# 3__Sensors.net
KiCad netlist of a schematic drawn in Altium Designer
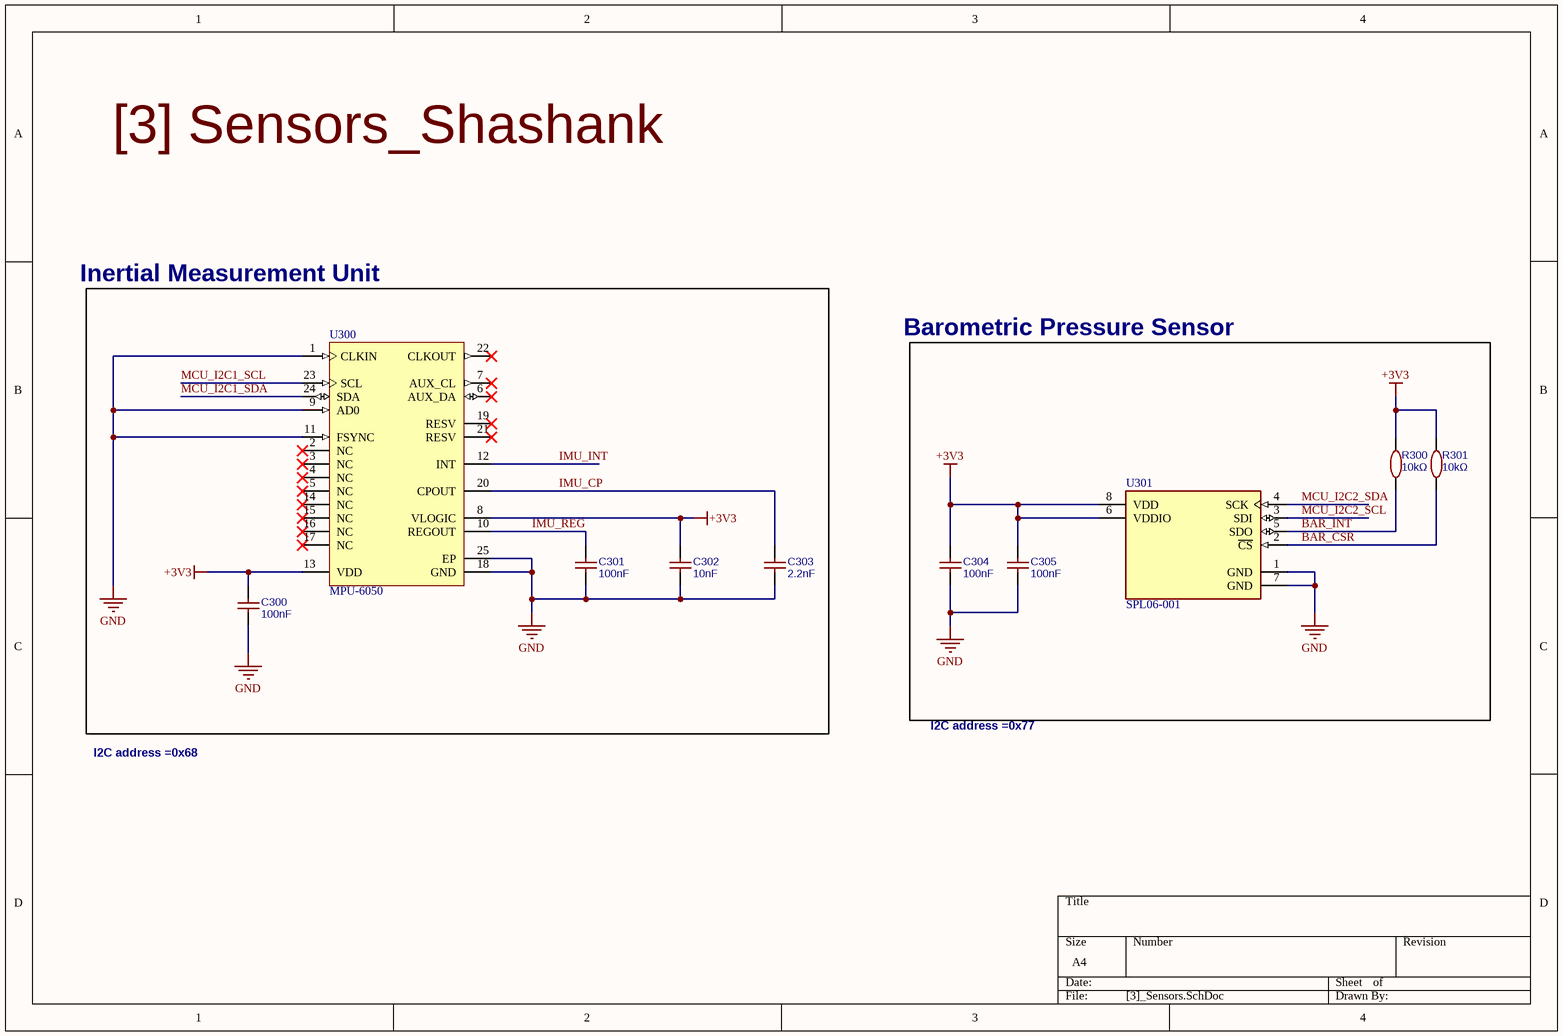
[diagram p0: [3]_Sensors.SchDoc]

(export (version "E")
  (design (tool "Eeschema 10.0.6"))
  (components
    (comp (ref "C300")
      (value "100nF")
      (footprint "C0402")
      (fields (field (name "MANUFACTURER") "FH(风华)") (field (name "MANUFACTURER PART") "0402B471K500NT"))
      (libsource (lib "Power_Lib") (part "470pF"))
    )
    (comp (ref "C301")
      (value "100nF")
      (footprint "C0402")
      (fields (field (name "MANUFACTURER") "FH(风华)") (field (name "MANUFACTURER PART") "0402B471K500NT"))
      (libsource (lib "Power_Lib") (part "470pF"))
    )
    (comp (ref "C302")
      (value "10nF")
      (footprint "C0402")
      (fields (field (name "MANUFACTURER") "FH(风华)") (field (name "MANUFACTURER PART") "0402B471K500NT"))
      (libsource (lib "Power_Lib") (part "470pF"))
    )
    (comp (ref "C303")
      (value "2.2nF")
      (footprint "C0402")
      (fields (field (name "MANUFACTURER") "FH(风华)") (field (name "MANUFACTURER PART") "0402B471K500NT"))
      (libsource (lib "Power_Lib") (part "470pF"))
    )
    (comp (ref "C304")
      (value "100nF")
      (footprint "C0402")
      (fields (field (name "MANUFACTURER") "FH(风华)") (field (name "MANUFACTURER PART") "0402B471K500NT"))
      (libsource (lib "Power_Lib") (part "470pF"))
    )
    (comp (ref "C305")
      (value "100nF")
      (footprint "C0402")
      (fields (field (name "MANUFACTURER") "FH(风华)") (field (name "MANUFACTURER PART") "0402B471K500NT"))
      (libsource (lib "Power_Lib") (part "470pF"))
    )
    (comp (ref "R300")
      (value "10kΩ")
      (footprint "R0402")
      (fields
        (field (name "MANUFACTURER") "UNI-ROYAL(厚声)")
        (field (name "MANUFACTURER PART") "0402WGF1001TCE")
      )
      (libsource (lib "Power_Lib") (part "1kΩ"))
    )
    (comp (ref "R301")
      (value "10kΩ")
      (footprint "R0402")
      (fields
        (field (name "MANUFACTURER") "UNI-ROYAL(厚声)")
        (field (name "MANUFACTURER PART") "0402WGF1001TCE")
      )
      (libsource (lib "Power_Lib") (part "1kΩ"))
    )
    (comp (ref "U300")
      (value "MPU-6050")
      (footprint "IS-QFN-24_V")
      (fields (field (name "MANUFACTURER") "InvenSense"))
      (libsource (lib "Altium Content Vault") (part "IS-MPU-6050-QFN-24"))
    )
    (comp (ref "U301")
      (value "SPL06-001")
      (footprint "FP-BMP280-MFG")
      (description "SENSOR PRESSURE ABS")
      (libsource (lib "Altium Content Vault") (part "69b1aacbb03d82763a43fac02afba64"))
    )
  )
  (nets
    (net (code "1") (name "+3V3") (class "Default")
      (node (ref "C300") (pin "2") (pinfunction "2_2") (pintype "passive"))
      (node (ref "C302") (pin "2") (pinfunction "2_2") (pintype "passive"))
      (node (ref "C304") (pin "2") (pinfunction "2_2") (pintype "passive"))
      (node (ref "C305") (pin "2") (pinfunction "2_2") (pintype "passive"))
      (node (ref "R300") (pin "2") (pinfunction "2_2") (pintype "passive"))
      (node (ref "R301") (pin "2") (pinfunction "2_2") (pintype "passive"))
      (node (ref "U300") (pin "13") (pinfunction "VDD_13") (pintype "power_in"))
      (node (ref "U300") (pin "8") (pinfunction "VLOGIC_8") (pintype "power_in"))
      (node (ref "U301") (pin "6") (pinfunction "VDDIO_6") (pintype "power_in"))
      (node (ref "U301") (pin "8") (pinfunction "VDD_8") (pintype "power_in"))
    )
    (net (code "2") (name "/BAR_CSR") (class "Default")
      (node (ref "R301") (pin "1") (pinfunction "1_1") (pintype "passive"))
      (node (ref "U301") (pin "2") (pinfunction "~{CS}_2") (pintype "input"))
    )
    (net (code "3") (name "/BAR_INT") (class "Default")
      (node (ref "R300") (pin "1") (pinfunction "1_1") (pintype "passive"))
      (node (ref "U301") (pin "5") (pinfunction "SDO_5") (pintype "bidirectional"))
    )
    (net (code "4") (name "/IMU_CP") (class "Default")
      (node (ref "C303") (pin "2") (pinfunction "2_2") (pintype "passive"))
      (node (ref "U300") (pin "20") (pinfunction "CPOUT_20") (pintype "passive"))
    )
    (net (code "5") (name "/IMU_INT") (class "Default")
      (node (ref "U300") (pin "12") (pinfunction "INT_12") (pintype "open_collector"))
    )
    (net (code "6") (name "/IMU_REG") (class "Default")
      (node (ref "C301") (pin "2") (pinfunction "2_2") (pintype "passive"))
      (node (ref "U300") (pin "10") (pinfunction "REGOUT_10") (pintype "passive"))
    )
    (net (code "7") (name "/MCU_I2C1_SCL") (class "Default")
      (node (ref "U300") (pin "23") (pinfunction "SCL_23") (pintype "input"))
    )
    (net (code "8") (name "/MCU_I2C1_SDA") (class "Default")
      (node (ref "U300") (pin "24") (pinfunction "SDA_24") (pintype "bidirectional"))
    )
    (net (code "9") (name "/MCU_I2C2_SCL") (class "Default")
      (node (ref "U301") (pin "3") (pinfunction "SDI_3") (pintype "bidirectional"))
    )
    (net (code "10") (name "/MCU_I2C2_SDA") (class "Default")
      (node (ref "U301") (pin "4") (pinfunction "SCK_4") (pintype "input"))
    )
    (net (code "11") (name "GND") (class "Default")
      (node (ref "C300") (pin "1") (pinfunction "1_1") (pintype "passive"))
      (node (ref "C301") (pin "1") (pinfunction "1_1") (pintype "passive"))
      (node (ref "C302") (pin "1") (pinfunction "1_1") (pintype "passive"))
      (node (ref "C303") (pin "1") (pinfunction "1_1") (pintype "passive"))
      (node (ref "C304") (pin "1") (pinfunction "1_1") (pintype "passive"))
      (node (ref "C305") (pin "1") (pinfunction "1_1") (pintype "passive"))
      (node (ref "U300") (pin "1") (pinfunction "CLKIN_1") (pintype "input"))
      (node (ref "U300") (pin "11") (pinfunction "FSYNC_11") (pintype "input"))
      (node (ref "U300") (pin "18") (pinfunction "GND_18") (pintype "power_in"))
      (node (ref "U300") (pin "25") (pinfunction "EP_25") (pintype "power_in"))
      (node (ref "U300") (pin "9") (pinfunction "AD0_9") (pintype "input"))
      (node (ref "U301") (pin "1") (pinfunction "GND_1") (pintype "power_in"))
      (node (ref "U301") (pin "7") (pinfunction "GND_7") (pintype "power_in"))
    )
    (net (code "12") (name "unconnected-(U300-AUX_CL-Pad7)") (class "Default")
      (node (ref "U300") (pin "7") (pinfunction "AUX_CL_7") (pintype "output+no_connect"))
    )
    (net (code "13") (name "unconnected-(U300-AUX_DA-Pad6)") (class "Default")
      (node (ref "U300") (pin "6") (pinfunction "AUX_DA_6") (pintype "bidirectional+no_connect"))
    )
    (net (code "14") (name "unconnected-(U300-CLKOUT-Pad22)") (class "Default")
      (node (ref "U300") (pin "22") (pinfunction "CLKOUT_22") (pintype "output+no_connect"))
    )
    (net (code "15") (name "unconnected-(U300-NC-Pad2)") (class "Default")
      (node (ref "U300") (pin "2") (pinfunction "NC_2") (pintype "passive+no_connect"))
    )
    (net (code "16") (name "unconnected-(U300-NC-Pad3)") (class "Default")
      (node (ref "U300") (pin "3") (pinfunction "NC_3") (pintype "passive+no_connect"))
    )
    (net (code "17") (name "unconnected-(U300-NC-Pad4)") (class "Default")
      (node (ref "U300") (pin "4") (pinfunction "NC_4") (pintype "passive+no_connect"))
    )
    (net (code "18") (name "unconnected-(U300-NC-Pad5)") (class "Default")
      (node (ref "U300") (pin "5") (pinfunction "NC_5") (pintype "passive+no_connect"))
    )
    (net (code "19") (name "unconnected-(U300-NC-Pad14)") (class "Default")
      (node (ref "U300") (pin "14") (pinfunction "NC_14") (pintype "passive+no_connect"))
    )
    (net (code "20") (name "unconnected-(U300-NC-Pad15)") (class "Default")
      (node (ref "U300") (pin "15") (pinfunction "NC_15") (pintype "passive+no_connect"))
    )
    (net (code "21") (name "unconnected-(U300-NC-Pad16)") (class "Default")
      (node (ref "U300") (pin "16") (pinfunction "NC_16") (pintype "passive+no_connect"))
    )
    (net (code "22") (name "unconnected-(U300-NC-Pad17)") (class "Default")
      (node (ref "U300") (pin "17") (pinfunction "NC_17") (pintype "passive+no_connect"))
    )
    (net (code "23") (name "unconnected-(U300-RESV-Pad19)") (class "Default")
      (node (ref "U300") (pin "19") (pinfunction "RESV_19") (pintype "passive+no_connect"))
    )
    (net (code "24") (name "unconnected-(U300-RESV-Pad21)") (class "Default")
      (node (ref "U300") (pin "21") (pinfunction "RESV_21") (pintype "passive+no_connect"))
    )
  )
)
